# ASD2511.net
KiCad netlist of a schematic drawn in EAGLE
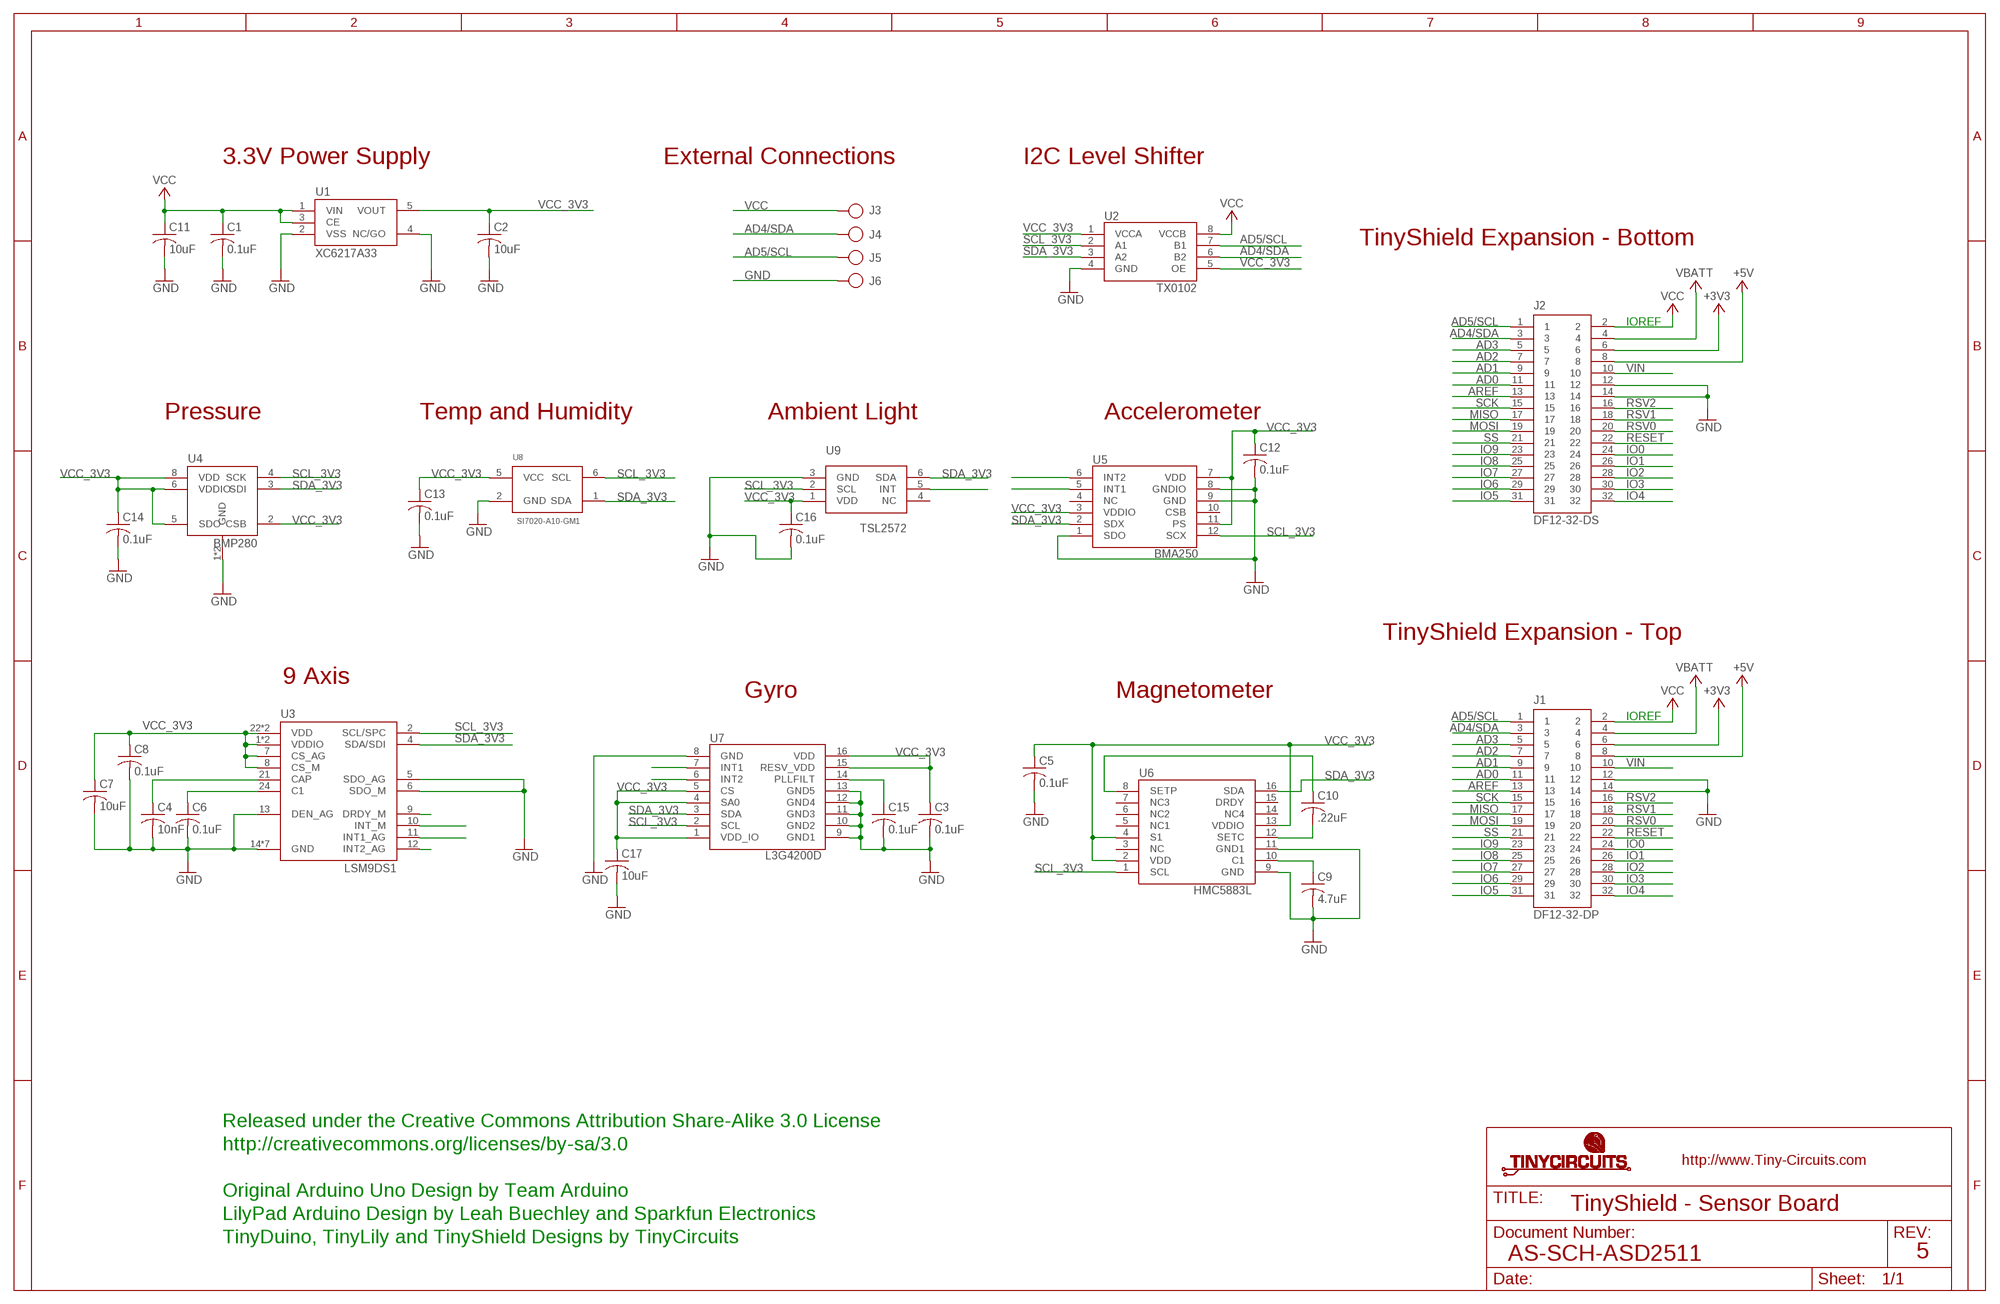
[diagram p0: schematic, sheet 1]

(export (version "E")
  (design (tool "Eeschema 10.0.6"))
  (components
    (comp (ref "C1")
      (value "0.1uF")
      (footprint "eagle-import:C0402")
      (fields (field (name "PARTNO") "AS-ITM-00008") (field (name "PARTNO_1") "AS-ITM-00008"))
      (libsource (lib "eagle-import") (part "AS-ITM-00008"))
    )
    (comp (ref "C2")
      (value "10uF")
      (footprint "eagle-import:C0603")
      (fields (field (name "PARTNO") "AS-ITM-00002") (field (name "PARTNO_1") "AS-ITM-00002"))
      (libsource (lib "eagle-import") (part "AS-ITM-00002"))
    )
    (comp (ref "C3")
      (value "0.1uF")
      (footprint "eagle-import:C0402")
      (fields (field (name "PARTNO") "AS-ITM-00008") (field (name "PARTNO_1") "AS-ITM-00008"))
      (libsource (lib "eagle-import") (part "AS-ITM-00008"))
    )
    (comp (ref "C4")
      (value "10nF")
      (footprint "eagle-import:C0402")
      (fields (field (name "PARTNO") "AS-ITM-00084"))
      (libsource (lib "eagle-import") (part "AS-ITM-00084"))
    )
    (comp (ref "C5")
      (value "0.1uF")
      (footprint "eagle-import:C0402")
      (fields (field (name "PARTNO") "AS-ITM-00008") (field (name "PARTNO_1") "AS-ITM-00008"))
      (libsource (lib "eagle-import") (part "AS-ITM-00008"))
    )
    (comp (ref "C6")
      (value "0.1uF")
      (footprint "eagle-import:C0402")
      (fields (field (name "PARTNO") "AS-ITM-00008"))
      (libsource (lib "eagle-import") (part "AS-ITM-00008"))
    )
    (comp (ref "C7")
      (value "10uF")
      (footprint "eagle-import:C0603")
      (fields (field (name "PARTNO") "AS-ITM-00002") (field (name "PARTNO_1") "AS-ITM-00002"))
      (libsource (lib "eagle-import") (part "AS-ITM-00002"))
    )
    (comp (ref "C8")
      (value "0.1uF")
      (footprint "eagle-import:C0402")
      (fields (field (name "PARTNO") "AS-ITM-00008") (field (name "PARTNO_1") "AS-ITM-00008"))
      (libsource (lib "eagle-import") (part "AS-ITM-00008"))
    )
    (comp (ref "C9")
      (value "4.7uF")
      (footprint "eagle-import:C0402")
      (fields (field (name "PARTNO") "AS-ITM-00242") (field (name "PARTNO_1") "AS-ITM-00242"))
      (libsource (lib "eagle-import") (part "AS-ITM-00242"))
    )
    (comp (ref "C10")
      (value ".22uF")
      (footprint "eagle-import:C0402")
      (fields (field (name "PARTNO") "AS-ITM-00087"))
      (libsource (lib "eagle-import") (part "AS-ITM-00087"))
    )
    (comp (ref "C11")
      (value "10uF")
      (footprint "eagle-import:C0603")
      (fields (field (name "PARTNO") "AS-ITM-00002"))
      (libsource (lib "eagle-import") (part "AS-ITM-00002"))
    )
    (comp (ref "C12")
      (value "0.1uF")
      (footprint "eagle-import:C0402")
      (fields (field (name "PARTNO") "AS-ITM-00008") (field (name "PARTNO_1") "AS-ITM-00008"))
      (libsource (lib "eagle-import") (part "AS-ITM-00008"))
    )
    (comp (ref "C13")
      (value "0.1uF")
      (footprint "eagle-import:C0402")
      (fields (field (name "PARTNO") "AS-ITM-00008") (field (name "PARTNO_1") "AS-ITM-00008"))
      (libsource (lib "eagle-import") (part "AS-ITM-00008"))
    )
    (comp (ref "C14")
      (value "0.1uF")
      (footprint "eagle-import:C0402")
      (fields (field (name "PARTNO") "AS-ITM-00008") (field (name "PARTNO_1") "AS-ITM-00008"))
      (libsource (lib "eagle-import") (part "AS-ITM-00008"))
    )
    (comp (ref "C15")
      (value "0.1uF")
      (footprint "eagle-import:C0402")
      (fields (field (name "PARTNO") "AS-ITM-00008") (field (name "PARTNO_1") "AS-ITM-00008"))
      (libsource (lib "eagle-import") (part "AS-ITM-00008"))
    )
    (comp (ref "C16")
      (value "0.1uF")
      (footprint "eagle-import:C0402")
      (fields (field (name "PARTNO") "AS-ITM-00008") (field (name "PARTNO_1") "AS-ITM-00008"))
      (libsource (lib "eagle-import") (part "AS-ITM-00008"))
    )
    (comp (ref "C17")
      (value "10uF")
      (footprint "eagle-import:C0603")
      (fields (field (name "PARTNO") "AS-ITM-00002"))
      (libsource (lib "eagle-import") (part "AS-ITM-00002"))
    )
    (comp (ref "J1")
      (value "DF12-32-DP")
      (footprint "eagle-import:DF12-32-DP")
      (fields (field (name "PARTNO") "AS-ITM-00015") (field (name "PARTNO_1") "AS-ITM-00015"))
      (libsource (lib "eagle-import") (part "AS-ITM-00015"))
    )
    (comp (ref "J2")
      (value "DF12-32-DS")
      (footprint "eagle-import:DF12-32-DS")
      (fields (field (name "PARTNO") "AS-ITM-00012") (field (name "PARTNO_1") "AS-ITM-00012"))
      (libsource (lib "eagle-import") (part "AS-ITM-00012"))
    )
    (comp (ref "J3")
      (value "PIN_1X.1\"1")
      (footprint "eagle-import:1X.1__2")
      (libsource (lib "eagle-import") (part "PIN_1X.1{dblquote}1"))
    )
    (comp (ref "J4")
      (value "PIN_1X.1\"1")
      (footprint "eagle-import:1X.1__2")
      (libsource (lib "eagle-import") (part "PIN_1X.1{dblquote}1"))
    )
    (comp (ref "J5")
      (value "PIN_1X.1\"1")
      (footprint "eagle-import:1X.1__2")
      (libsource (lib "eagle-import") (part "PIN_1X.1{dblquote}1"))
    )
    (comp (ref "J6")
      (value "PIN_1X.1\"1")
      (footprint "eagle-import:1X.1__2")
      (libsource (lib "eagle-import") (part "PIN_1X.1{dblquote}1"))
    )
    (comp (ref "U1")
      (value "XC6217A33")
      (footprint "eagle-import:SOT-25")
      (fields (field (name "PARTNO") "AS-ITM-00249") (field (name "PARTNO_1") "AS-ITM-00249"))
      (libsource (lib "eagle-import") (part "AS-ITM-00249"))
    )
    (comp (ref "U2")
      (value "TX0102")
      (footprint "eagle-import:DQE(R-PX2SON-N8)")
      (fields (field (name "PARTNO") "AS-ITM-00073"))
      (libsource (lib "eagle-import") (part "AS-ITM-00073"))
    )
    (comp (ref "U3")
      (value "LSM9DS1")
      (footprint "eagle-import:LGA-24")
      (fields (field (name "PARTNO") "AS-ITM-00265"))
      (libsource (lib "eagle-import") (part "AS-ITM-00265"))
    )
    (comp (ref "U4")
      (value "BMP280")
      (footprint "eagle-import:BMP280")
      (fields (field (name "PARTNO") "AS-ITM-00264"))
      (libsource (lib "eagle-import") (part "AS-ITM-00264"))
    )
    (comp (ref "U5")
      (value "BMA250")
      (footprint "eagle-import:3-AXIS_ACCELEROMETER")
      (fields (field (name "PARTNO") "AS-ITM-00070"))
      (libsource (lib "eagle-import") (part "AS-ITM-00070"))
    )
    (comp (ref "U6")
      (value "HMC5883L")
      (footprint "eagle-import:HMC5883L")
      (fields (field (name "PARTNO") "AS-ITM-00086"))
      (libsource (lib "eagle-import") (part "AS-ITM-00086"))
    )
    (comp (ref "U7")
      (value "L3G4200D")
      (footprint "eagle-import:L3G4200D")
      (fields (field (name "PARTNO") "AS-ITM-00089"))
      (libsource (lib "eagle-import") (part "AS-ITM-00089"))
    )
    (comp (ref "U8")
      (value "SI7020-A10-GM1")
      (footprint "eagle-import:DFN6")
      (fields (field (name "PARTNO") "AS-ITM-00218"))
      (libsource (lib "eagle-import") (part "AS-ITM-00218"))
    )
    (comp (ref "U9")
      (value "TSL2572")
      (footprint "eagle-import:TSL2572")
      (fields (field (name "PARTNO") "AS-ITM-00116"))
      (libsource (lib "eagle-import") (part "AS-ITM-00116"))
    )
  )
  (nets
    (net (code "1") (name "+3V3") (class "Default")
      (node (ref "J1") (pin "6") (pinfunction "6_6") (pintype "bidirectional"))
      (node (ref "J2") (pin "6") (pinfunction "6_6") (pintype "bidirectional"))
    )
    (net (code "2") (name "+5V") (class "Default")
      (node (ref "J1") (pin "8") (pinfunction "8_8") (pintype "bidirectional"))
      (node (ref "J2") (pin "8") (pinfunction "8_8") (pintype "bidirectional"))
    )
    (net (code "3") (name "/AD0") (class "Default")
      (node (ref "J1") (pin "11") (pinfunction "11_11") (pintype "bidirectional"))
      (node (ref "J2") (pin "11") (pinfunction "11_11") (pintype "bidirectional"))
    )
    (net (code "4") (name "/AD1") (class "Default")
      (node (ref "J1") (pin "9") (pinfunction "9_9") (pintype "bidirectional"))
      (node (ref "J2") (pin "9") (pinfunction "9_9") (pintype "bidirectional"))
    )
    (net (code "5") (name "/AD2") (class "Default")
      (node (ref "J1") (pin "7") (pinfunction "7_7") (pintype "bidirectional"))
      (node (ref "J2") (pin "7") (pinfunction "7_7") (pintype "bidirectional"))
    )
    (net (code "6") (name "/AD3") (class "Default")
      (node (ref "J1") (pin "5") (pinfunction "5_5") (pintype "bidirectional"))
      (node (ref "J2") (pin "5") (pinfunction "5_5") (pintype "bidirectional"))
    )
    (net (code "7") (name "/AD4{slash}SDA") (class "Default")
      (node (ref "J1") (pin "3") (pinfunction "3_3") (pintype "bidirectional"))
      (node (ref "J2") (pin "3") (pinfunction "3_3") (pintype "bidirectional"))
      (node (ref "J4") (pin "1") (pinfunction "1_1") (pintype "bidirectional"))
      (node (ref "U2") (pin "6") (pinfunction "B2_6") (pintype "bidirectional"))
    )
    (net (code "8") (name "/AD5{slash}SCL") (class "Default")
      (node (ref "J1") (pin "1") (pinfunction "1_1") (pintype "bidirectional"))
      (node (ref "J2") (pin "1") (pinfunction "1_1") (pintype "bidirectional"))
      (node (ref "J5") (pin "1") (pinfunction "1_1") (pintype "bidirectional"))
      (node (ref "U2") (pin "7") (pinfunction "B1_7") (pintype "bidirectional"))
    )
    (net (code "9") (name "/AREF") (class "Default")
      (node (ref "J1") (pin "13") (pinfunction "13_13") (pintype "bidirectional"))
      (node (ref "J2") (pin "13") (pinfunction "13_13") (pintype "bidirectional"))
    )
    (net (code "10") (name "/IO0") (class "Default")
      (node (ref "J1") (pin "24") (pinfunction "24_24") (pintype "bidirectional"))
      (node (ref "J2") (pin "24") (pinfunction "24_24") (pintype "bidirectional"))
    )
    (net (code "11") (name "/IO1") (class "Default")
      (node (ref "J1") (pin "26") (pinfunction "26_26") (pintype "bidirectional"))
      (node (ref "J2") (pin "26") (pinfunction "26_26") (pintype "bidirectional"))
    )
    (net (code "12") (name "/IO2") (class "Default")
      (node (ref "J1") (pin "28") (pinfunction "28_28") (pintype "bidirectional"))
      (node (ref "J2") (pin "28") (pinfunction "28_28") (pintype "bidirectional"))
    )
    (net (code "13") (name "/IO3") (class "Default")
      (node (ref "J1") (pin "30") (pinfunction "30_30") (pintype "bidirectional"))
      (node (ref "J2") (pin "30") (pinfunction "30_30") (pintype "bidirectional"))
    )
    (net (code "14") (name "/IO4") (class "Default")
      (node (ref "J1") (pin "32") (pinfunction "32_32") (pintype "bidirectional"))
      (node (ref "J2") (pin "32") (pinfunction "32_32") (pintype "bidirectional"))
    )
    (net (code "15") (name "/IO5") (class "Default")
      (node (ref "J1") (pin "31") (pinfunction "31_31") (pintype "bidirectional"))
      (node (ref "J2") (pin "31") (pinfunction "31_31") (pintype "bidirectional"))
    )
    (net (code "16") (name "/IO6") (class "Default")
      (node (ref "J1") (pin "29") (pinfunction "29_29") (pintype "bidirectional"))
      (node (ref "J2") (pin "29") (pinfunction "29_29") (pintype "bidirectional"))
    )
    (net (code "17") (name "/IO7") (class "Default")
      (node (ref "J1") (pin "27") (pinfunction "27_27") (pintype "bidirectional"))
      (node (ref "J2") (pin "27") (pinfunction "27_27") (pintype "bidirectional"))
    )
    (net (code "18") (name "/IO8") (class "Default")
      (node (ref "J1") (pin "25") (pinfunction "25_25") (pintype "bidirectional"))
      (node (ref "J2") (pin "25") (pinfunction "25_25") (pintype "bidirectional"))
    )
    (net (code "19") (name "/IO9") (class "Default")
      (node (ref "J1") (pin "23") (pinfunction "23_23") (pintype "bidirectional"))
      (node (ref "J2") (pin "23") (pinfunction "23_23") (pintype "bidirectional"))
    )
    (net (code "20") (name "/MISO") (class "Default")
      (node (ref "J1") (pin "17") (pinfunction "17_17") (pintype "bidirectional"))
      (node (ref "J2") (pin "17") (pinfunction "17_17") (pintype "bidirectional"))
    )
    (net (code "21") (name "/MOSI") (class "Default")
      (node (ref "J1") (pin "19") (pinfunction "19_19") (pintype "bidirectional"))
      (node (ref "J2") (pin "19") (pinfunction "19_19") (pintype "bidirectional"))
    )
    (net (code "22") (name "/RESET") (class "Default")
      (node (ref "J1") (pin "22") (pinfunction "22_22") (pintype "bidirectional"))
      (node (ref "J2") (pin "22") (pinfunction "22_22") (pintype "bidirectional"))
    )
    (net (code "23") (name "/RSV0") (class "Default")
      (node (ref "J1") (pin "20") (pinfunction "20_20") (pintype "bidirectional"))
      (node (ref "J2") (pin "20") (pinfunction "20_20") (pintype "bidirectional"))
    )
    (net (code "24") (name "/RSV1") (class "Default")
      (node (ref "J1") (pin "18") (pinfunction "18_18") (pintype "bidirectional"))
      (node (ref "J2") (pin "18") (pinfunction "18_18") (pintype "bidirectional"))
    )
    (net (code "25") (name "/RSV2") (class "Default")
      (node (ref "J1") (pin "16") (pinfunction "16_16") (pintype "bidirectional"))
      (node (ref "J2") (pin "16") (pinfunction "16_16") (pintype "bidirectional"))
    )
    (net (code "26") (name "/SCK") (class "Default")
      (node (ref "J1") (pin "15") (pinfunction "15_15") (pintype "bidirectional"))
      (node (ref "J2") (pin "15") (pinfunction "15_15") (pintype "bidirectional"))
    )
    (net (code "27") (name "/SCL_3V3") (class "Default")
      (node (ref "U2") (pin "2") (pinfunction "A1_2") (pintype "bidirectional"))
      (node (ref "U3") (pin "2") (pinfunction "SCL/SPC_2") (pintype "bidirectional"))
      (node (ref "U4") (pin "4") (pinfunction "SCK_4") (pintype "bidirectional"))
      (node (ref "U5") (pin "12") (pinfunction "SCX_12") (pintype "bidirectional"))
      (node (ref "U6") (pin "1") (pinfunction "SCL_1") (pintype "bidirectional"))
      (node (ref "U7") (pin "2") (pinfunction "SCL_2") (pintype "bidirectional"))
      (node (ref "U8") (pin "6") (pinfunction "SCL_6") (pintype "bidirectional"))
      (node (ref "U9") (pin "2") (pinfunction "SCL_2") (pintype "bidirectional"))
    )
    (net (code "28") (name "/SDA_3V3") (class "Default")
      (node (ref "U2") (pin "3") (pinfunction "A2_3") (pintype "bidirectional"))
      (node (ref "U3") (pin "4") (pinfunction "SDA/SDI_4") (pintype "bidirectional"))
      (node (ref "U4") (pin "3") (pinfunction "SDI_3") (pintype "bidirectional"))
      (node (ref "U5") (pin "2") (pinfunction "SDX_2") (pintype "bidirectional"))
      (node (ref "U6") (pin "16") (pinfunction "SDA_16") (pintype "bidirectional"))
      (node (ref "U7") (pin "3") (pinfunction "SDA_3") (pintype "bidirectional"))
      (node (ref "U8") (pin "1") (pinfunction "SDA_1") (pintype "bidirectional"))
      (node (ref "U9") (pin "6") (pinfunction "SDA_6") (pintype "bidirectional"))
    )
    (net (code "29") (name "/SS") (class "Default")
      (node (ref "J1") (pin "21") (pinfunction "21_21") (pintype "bidirectional"))
      (node (ref "J2") (pin "21") (pinfunction "21_21") (pintype "bidirectional"))
    )
    (net (code "30") (name "/VCC_3V3") (class "Default")
      (node (ref "C12") (pin "1") (pinfunction "1_1") (pintype "passive"))
      (node (ref "C13") (pin "1") (pinfunction "1_1") (pintype "passive"))
      (node (ref "C14") (pin "1") (pinfunction "1_1") (pintype "passive"))
      (node (ref "C16") (pin "1") (pinfunction "1_1") (pintype "passive"))
      (node (ref "C17") (pin "1") (pinfunction "1_1") (pintype "passive"))
      (node (ref "C2") (pin "1") (pinfunction "1_1") (pintype "passive"))
      (node (ref "C3") (pin "1") (pinfunction "1_1") (pintype "passive"))
      (node (ref "C5") (pin "1") (pinfunction "1_1") (pintype "passive"))
      (node (ref "C7") (pin "1") (pinfunction "1_1") (pintype "passive"))
      (node (ref "C8") (pin "1") (pinfunction "1_1") (pintype "passive"))
      (node (ref "U1") (pin "5") (pinfunction "VOUT_5") (pintype "bidirectional"))
      (node (ref "U2") (pin "1") (pinfunction "VCCA_1") (pintype "bidirectional"))
      (node (ref "U2") (pin "5") (pinfunction "OE_5") (pintype "bidirectional"))
      (node (ref "U3") (pin "1") (pinfunction "VDDIO_1") (pintype "bidirectional"))
      (node (ref "U3") (pin "22") (pinfunction "VDD_22") (pintype "bidirectional"))
      (node (ref "U3") (pin "23") (pinfunction "VDD_23") (pintype "bidirectional"))
      (node (ref "U3") (pin "3") (pinfunction "VDDIO_3") (pintype "bidirectional"))
      (node (ref "U3") (pin "7") (pinfunction "CS_AG_7") (pintype "bidirectional"))
      (node (ref "U3") (pin "8") (pinfunction "CS_M_8") (pintype "bidirectional"))
      (node (ref "U4") (pin "2") (pinfunction "CSB_2") (pintype "bidirectional"))
      (node (ref "U4") (pin "5") (pinfunction "SDO_5") (pintype "bidirectional"))
      (node (ref "U4") (pin "6") (pinfunction "VDDIO_6") (pintype "bidirectional"))
      (node (ref "U4") (pin "8") (pinfunction "VDD_8") (pintype "bidirectional"))
      (node (ref "U5") (pin "11") (pinfunction "PS_11") (pintype "bidirectional"))
      (node (ref "U5") (pin "3") (pinfunction "VDDIO_3") (pintype "bidirectional"))
      (node (ref "U5") (pin "7") (pinfunction "VDD_7") (pintype "bidirectional"))
      (node (ref "U6") (pin "13") (pinfunction "VDDIO_13") (pintype "bidirectional"))
      (node (ref "U6") (pin "2") (pinfunction "VDD_2") (pintype "bidirectional"))
      (node (ref "U6") (pin "4") (pinfunction "S1_4") (pintype "bidirectional"))
      (node (ref "U7") (pin "1") (pinfunction "VDD_IO_1") (pintype "bidirectional"))
      (node (ref "U7") (pin "15") (pinfunction "RESV_VDD_15") (pintype "bidirectional"))
      (node (ref "U7") (pin "16") (pinfunction "VDD_16") (pintype "bidirectional"))
      (node (ref "U7") (pin "4") (pinfunction "SA0_4") (pintype "bidirectional"))
      (node (ref "U7") (pin "5") (pinfunction "CS_5") (pintype "bidirectional"))
      (node (ref "U8") (pin "5") (pinfunction "VCC_5") (pintype "bidirectional"))
      (node (ref "U9") (pin "1") (pinfunction "VDD_1") (pintype "bidirectional"))
    )
    (net (code "31") (name "/VIN") (class "Default")
      (node (ref "J1") (pin "10") (pinfunction "10_10") (pintype "bidirectional"))
      (node (ref "J2") (pin "10") (pinfunction "10_10") (pintype "bidirectional"))
    )
    (net (code "32") (name "GND") (class "Default")
      (node (ref "C1") (pin "2") (pinfunction "2_2") (pintype "passive"))
      (node (ref "C11") (pin "2") (pinfunction "2_2") (pintype "passive"))
      (node (ref "C12") (pin "2") (pinfunction "2_2") (pintype "passive"))
      (node (ref "C13") (pin "2") (pinfunction "2_2") (pintype "passive"))
      (node (ref "C14") (pin "2") (pinfunction "2_2") (pintype "passive"))
      (node (ref "C15") (pin "2") (pinfunction "2_2") (pintype "passive"))
      (node (ref "C16") (pin "2") (pinfunction "2_2") (pintype "passive"))
      (node (ref "C17") (pin "2") (pinfunction "2_2") (pintype "passive"))
      (node (ref "C2") (pin "2") (pinfunction "2_2") (pintype "passive"))
      (node (ref "C3") (pin "2") (pinfunction "2_2") (pintype "passive"))
      (node (ref "C4") (pin "2") (pinfunction "2_2") (pintype "passive"))
      (node (ref "C5") (pin "2") (pinfunction "2_2") (pintype "passive"))
      (node (ref "C6") (pin "2") (pinfunction "2_2") (pintype "passive"))
      (node (ref "C7") (pin "2") (pinfunction "2_2") (pintype "passive"))
      (node (ref "C8") (pin "2") (pinfunction "2_2") (pintype "passive"))
      (node (ref "C9") (pin "2") (pinfunction "2_2") (pintype "passive"))
      (node (ref "J1") (pin "12") (pinfunction "12_12") (pintype "bidirectional"))
      (node (ref "J1") (pin "14") (pinfunction "14_14") (pintype "bidirectional"))
      (node (ref "J2") (pin "12") (pinfunction "12_12") (pintype "bidirectional"))
      (node (ref "J2") (pin "14") (pinfunction "14_14") (pintype "bidirectional"))
      (node (ref "J6") (pin "1") (pinfunction "1_1") (pintype "bidirectional"))
      (node (ref "U1") (pin "2") (pinfunction "VSS_2") (pintype "power_in"))
      (node (ref "U1") (pin "4") (pinfunction "NC/GO_4") (pintype "bidirectional"))
      (node (ref "U2") (pin "4") (pinfunction "GND_4") (pintype "bidirectional"))
      (node (ref "U3") (pin "13") (pinfunction "DEN_AG_13") (pintype "bidirectional"))
      (node (ref "U3") (pin "14") (pinfunction "GND_14") (pintype "bidirectional"))
      (node (ref "U3") (pin "15") (pinfunction "GND_15") (pintype "bidirectional"))
      (node (ref "U3") (pin "16") (pinfunction "GND_16") (pintype "bidirectional"))
      (node (ref "U3") (pin "17") (pinfunction "GND_17") (pintype "bidirectional"))
      (node (ref "U3") (pin "18") (pinfunction "GND_18") (pintype "bidirectional"))
      (node (ref "U3") (pin "19") (pinfunction "GND_19") (pintype "bidirectional"))
      (node (ref "U3") (pin "20") (pinfunction "GND_20") (pintype "bidirectional"))
      (node (ref "U3") (pin "5") (pinfunction "SDO_AG_5") (pintype "bidirectional"))
      (node (ref "U3") (pin "6") (pinfunction "SDO_M_6") (pintype "bidirectional"))
      (node (ref "U4") (pin "1") (pinfunction "GND_1") (pintype "bidirectional"))
      (node (ref "U4") (pin "7") (pinfunction "GND_7") (pintype "bidirectional"))
      (node (ref "U5") (pin "1") (pinfunction "SDO_1") (pintype "bidirectional"))
      (node (ref "U5") (pin "8") (pinfunction "GNDIO_8") (pintype "bidirectional"))
      (node (ref "U5") (pin "9") (pinfunction "GND_9") (pintype "bidirectional"))
      (node (ref "U6") (pin "11") (pinfunction "GND1_11") (pintype "bidirectional"))
      (node (ref "U6") (pin "9") (pinfunction "GND_9") (pintype "bidirectional"))
      (node (ref "U7") (pin "10") (pinfunction "GND2_10") (pintype "bidirectional"))
      (node (ref "U7") (pin "11") (pinfunction "GND3_11") (pintype "bidirectional"))
      (node (ref "U7") (pin "12") (pinfunction "GND4_12") (pintype "bidirectional"))
      (node (ref "U7") (pin "13") (pinfunction "GND5_13") (pintype "bidirectional"))
      (node (ref "U7") (pin "8") (pinfunction "GND_8") (pintype "bidirectional"))
      (node (ref "U7") (pin "9") (pinfunction "GND1_9") (pintype "bidirectional"))
      (node (ref "U8") (pin "2") (pinfunction "GND_2") (pintype "bidirectional"))
      (node (ref "U9") (pin "3") (pinfunction "GND_3") (pintype "bidirectional"))
    )
    (net (code "33") (name "Net-(U3-C1)") (class "Default")
      (node (ref "C6") (pin "1") (pinfunction "1_1") (pintype "passive"))
      (node (ref "U3") (pin "24") (pinfunction "C1_24") (pintype "bidirectional"))
    )
    (net (code "34") (name "Net-(U3-CAP)") (class "Default")
      (node (ref "C4") (pin "1") (pinfunction "1_1") (pintype "passive"))
      (node (ref "U3") (pin "21") (pinfunction "CAP_21") (pintype "bidirectional"))
    )
    (net (code "35") (name "Net-(U6-C1)") (class "Default")
      (node (ref "C9") (pin "1") (pinfunction "1_1") (pintype "passive"))
      (node (ref "U6") (pin "10") (pinfunction "C1_10") (pintype "bidirectional"))
    )
    (net (code "36") (name "Net-(U6-SETC)") (class "Default")
      (node (ref "C10") (pin "2") (pinfunction "2_2") (pintype "passive"))
      (node (ref "U6") (pin "12") (pinfunction "SETC_12") (pintype "bidirectional"))
    )
    (net (code "37") (name "Net-(U6-SETP)") (class "Default")
      (node (ref "C10") (pin "1") (pinfunction "1_1") (pintype "passive"))
      (node (ref "U6") (pin "8") (pinfunction "SETP_8") (pintype "bidirectional"))
    )
    (net (code "38") (name "Net-(U7-PLLFILT)") (class "Default")
      (node (ref "C15") (pin "1") (pinfunction "1_1") (pintype "passive"))
      (node (ref "U7") (pin "14") (pinfunction "PLLFILT_14") (pintype "bidirectional"))
    )
    (net (code "39") (name "VBATT") (class "Default")
      (node (ref "J1") (pin "4") (pinfunction "4_4") (pintype "bidirectional"))
      (node (ref "J2") (pin "4") (pinfunction "4_4") (pintype "bidirectional"))
    )
    (net (code "40") (name "VCC") (class "Default")
      (node (ref "C1") (pin "1") (pinfunction "1_1") (pintype "passive"))
      (node (ref "C11") (pin "1") (pinfunction "1_1") (pintype "passive"))
      (node (ref "J1") (pin "2") (pinfunction "2_2") (pintype "bidirectional"))
      (node (ref "J2") (pin "2") (pinfunction "2_2") (pintype "bidirectional"))
      (node (ref "J3") (pin "1") (pinfunction "1_1") (pintype "bidirectional"))
      (node (ref "U1") (pin "1") (pinfunction "VIN_1") (pintype "bidirectional"))
      (node (ref "U1") (pin "3") (pinfunction "CE_3") (pintype "bidirectional"))
      (node (ref "U2") (pin "8") (pinfunction "VCCB_8") (pintype "bidirectional"))
    )
    (net (code "41") (name "unconnected-(U3-DRDY_M-Pad9)") (class "Default")
      (node (ref "U3") (pin "9") (pinfunction "DRDY_M_9") (pintype "bidirectional"))
    )
    (net (code "42") (name "unconnected-(U3-INT1_AG-Pad11)") (class "Default")
      (node (ref "U3") (pin "11") (pinfunction "INT1_AG_11") (pintype "bidirectional"))
    )
    (net (code "43") (name "unconnected-(U3-INT2_AG-Pad12)") (class "Default")
      (node (ref "U3") (pin "12") (pinfunction "INT2_AG_12") (pintype "bidirectional"))
    )
    (net (code "44") (name "unconnected-(U3-INT_M-Pad10)") (class "Default")
      (node (ref "U3") (pin "10") (pinfunction "INT_M_10") (pintype "bidirectional"))
    )
    (net (code "45") (name "unconnected-(U5-CSB-Pad10)") (class "Default")
      (node (ref "U5") (pin "10") (pinfunction "CSB_10") (pintype "bidirectional"))
    )
    (net (code "46") (name "unconnected-(U5-INT1-Pad5)") (class "Default")
      (node (ref "U5") (pin "5") (pinfunction "INT1_5") (pintype "bidirectional"))
    )
    (net (code "47") (name "unconnected-(U5-INT2-Pad6)") (class "Default")
      (node (ref "U5") (pin "6") (pinfunction "INT2_6") (pintype "bidirectional"))
    )
    (net (code "48") (name "unconnected-(U5-NC-Pad4)") (class "Default")
      (node (ref "U5") (pin "4") (pinfunction "NC_4") (pintype "bidirectional"))
    )
    (net (code "49") (name "unconnected-(U6-DRDY-Pad15)") (class "Default")
      (node (ref "U6") (pin "15") (pinfunction "DRDY_15") (pintype "bidirectional"))
    )
    (net (code "50") (name "unconnected-(U6-NC-Pad3)") (class "Default")
      (node (ref "U6") (pin "3") (pinfunction "NC_3") (pintype "bidirectional"))
    )
    (net (code "51") (name "unconnected-(U6-NC1-Pad5)") (class "Default")
      (node (ref "U6") (pin "5") (pinfunction "NC1_5") (pintype "bidirectional"))
    )
    (net (code "52") (name "unconnected-(U6-NC2-Pad6)") (class "Default")
      (node (ref "U6") (pin "6") (pinfunction "NC2_6") (pintype "bidirectional"))
    )
    (net (code "53") (name "unconnected-(U6-NC3-Pad7)") (class "Default")
      (node (ref "U6") (pin "7") (pinfunction "NC3_7") (pintype "bidirectional"))
    )
    (net (code "54") (name "unconnected-(U6-NC4-Pad14)") (class "Default")
      (node (ref "U6") (pin "14") (pinfunction "NC4_14") (pintype "bidirectional"))
    )
    (net (code "55") (name "unconnected-(U7-INT1-Pad7)") (class "Default")
      (node (ref "U7") (pin "7") (pinfunction "INT1_7") (pintype "bidirectional"))
    )
    (net (code "56") (name "unconnected-(U7-INT2-Pad6)") (class "Default")
      (node (ref "U7") (pin "6") (pinfunction "INT2_6") (pintype "bidirectional"))
    )
    (net (code "57") (name "unconnected-(U9-INT-Pad5)") (class "Default")
      (node (ref "U9") (pin "5") (pinfunction "INT_5") (pintype "bidirectional"))
    )
    (net (code "58") (name "unconnected-(U9-NC-Pad4)") (class "Default")
      (node (ref "U9") (pin "4") (pinfunction "NC_4") (pintype "bidirectional"))
    )
  )
)
